# SD_Card_-_Battery_Board.net
KiCad netlist of a schematic drawn in EAGLE
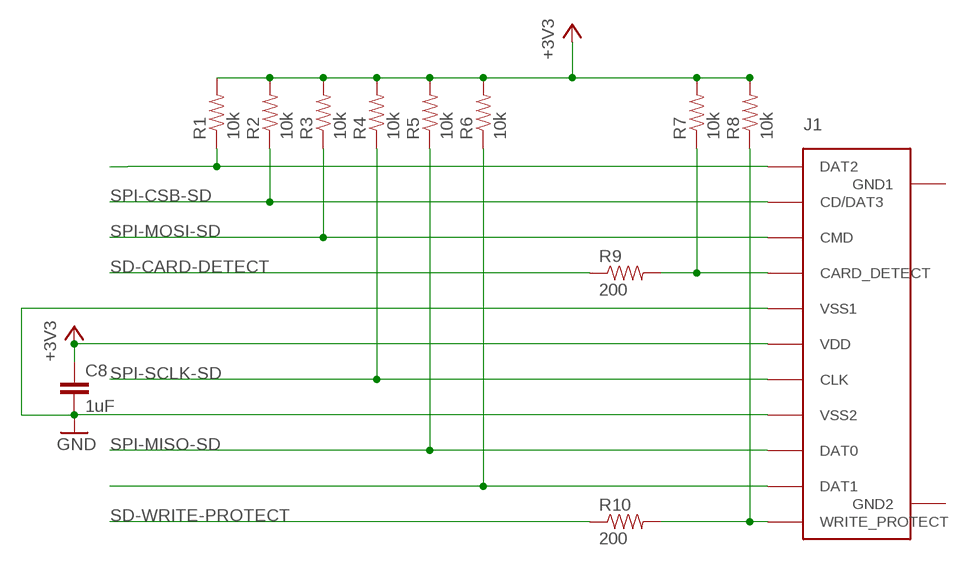
[diagram p0: schematic, sheet 1]
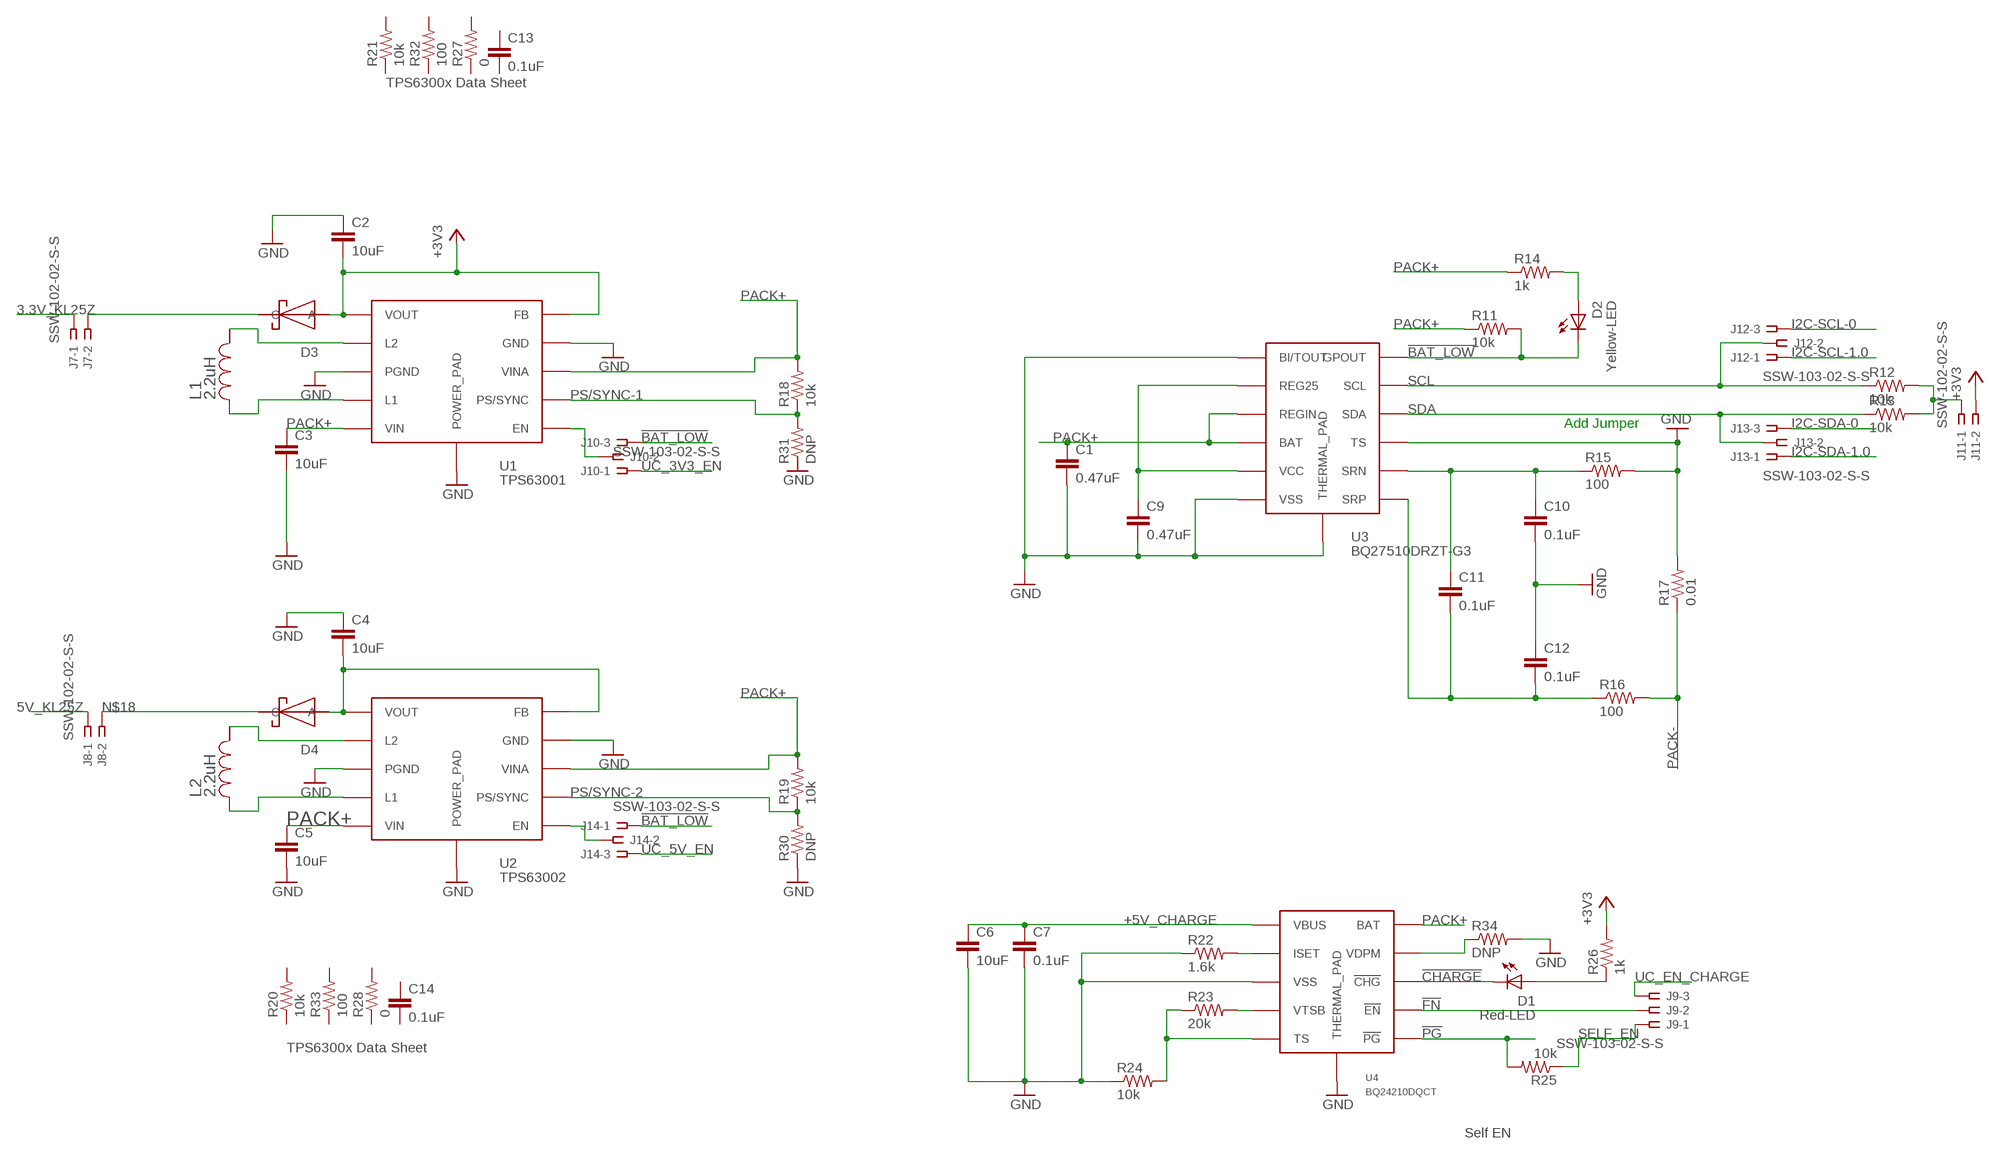
[diagram p1: schematic, sheet 2]
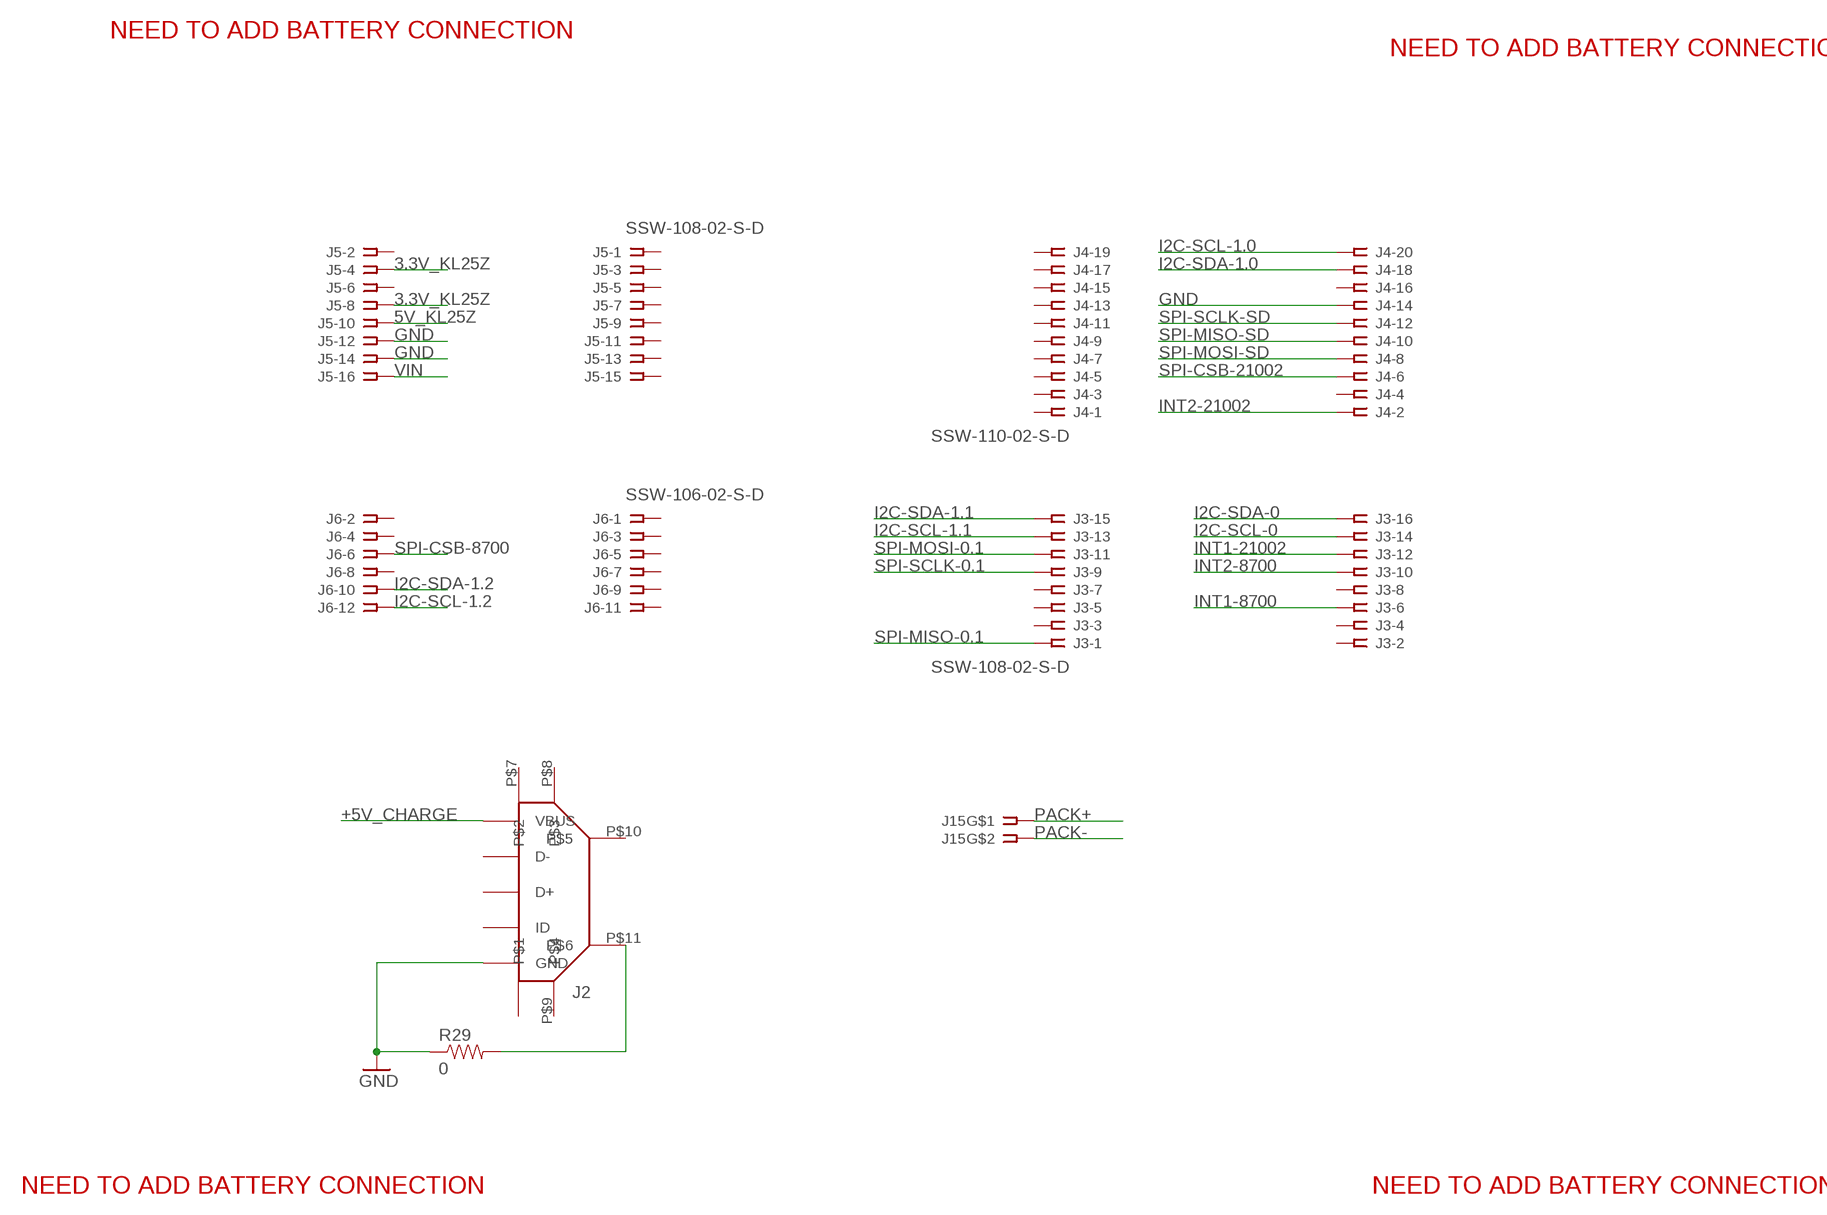
[diagram p2: schematic, sheet 3]

(export (version "E")
  (design (tool "Eeschema 10.0.6"))
  (components
    (comp (ref "C8")
      (value "1uF")
      (footprint "eagle-import:C0402")
      (fields
        (field (name "MANUFACTURER") "Johanson Dielectrics Inc.")
        (field (name "MANUFACTURER_PART_NUMBER") "100R07X105KV4T")
        (field (name "NEWARK_PART_NUMBER") "41T2953")
      )
      (libsource (lib "eagle-import") (part "CAPACITOR1U-X5R-10%-10V"))
    )
    (comp (ref "J1")
      (value "SD_CARD_SLOT")
      (footprint "eagle-import:693061010911")
      (fields
        (field (name "MANUFACTURER") "Wurth Electronik")
        (field (name "MANUFACTURER_PART_NUMBER") "693061010911")
        (field (name "NEWARK_PART_NUMBER") "89T9349")
      )
      (libsource (lib "eagle-import") (part "SD_CARD_SLOT"))
    )
    (comp (ref "R1")
      (value "10k")
      (footprint "eagle-import:R0603")
      (fields
        (field (name "MANUFACTURER") "Visay")
        (field (name "MANUFACTURER_PART_NUMBER") "TNPW060310K0DEEA")
        (field (name "NEWARK_PART_NUMBER") "84R1889")
      )
      (libsource (lib "eagle-import") (part "RESISTOR10K-100M-0.5%-75V"))
    )
    (comp (ref "R2")
      (value "10k")
      (footprint "eagle-import:R0603")
      (fields
        (field (name "MANUFACTURER") "Visay")
        (field (name "MANUFACTURER_PART_NUMBER") "TNPW060310K0DEEA")
        (field (name "NEWARK_PART_NUMBER") "84R1889")
      )
      (libsource (lib "eagle-import") (part "RESISTOR10K-100M-0.5%-75V"))
    )
    (comp (ref "R3")
      (value "10k")
      (footprint "eagle-import:R0603")
      (fields
        (field (name "MANUFACTURER") "Visay")
        (field (name "MANUFACTURER_PART_NUMBER") "TNPW060310K0DEEA")
        (field (name "NEWARK_PART_NUMBER") "84R1889")
      )
      (libsource (lib "eagle-import") (part "RESISTOR10K-100M-0.5%-75V"))
    )
    (comp (ref "R4")
      (value "10k")
      (footprint "eagle-import:R0603")
      (fields
        (field (name "MANUFACTURER") "Visay")
        (field (name "MANUFACTURER_PART_NUMBER") "TNPW060310K0DEEA")
        (field (name "NEWARK_PART_NUMBER") "84R1889")
      )
      (libsource (lib "eagle-import") (part "RESISTOR10K-100M-0.5%-75V"))
    )
    (comp (ref "R5")
      (value "10k")
      (footprint "eagle-import:R0603")
      (fields
        (field (name "MANUFACTURER") "Visay")
        (field (name "MANUFACTURER_PART_NUMBER") "TNPW060310K0DEEA")
        (field (name "NEWARK_PART_NUMBER") "84R1889")
      )
      (libsource (lib "eagle-import") (part "RESISTOR10K-100M-0.5%-75V"))
    )
    (comp (ref "R6")
      (value "10k")
      (footprint "eagle-import:R0603")
      (fields
        (field (name "MANUFACTURER") "Visay")
        (field (name "MANUFACTURER_PART_NUMBER") "TNPW060310K0DEEA")
        (field (name "NEWARK_PART_NUMBER") "84R1889")
      )
      (libsource (lib "eagle-import") (part "RESISTOR10K-100M-0.5%-75V"))
    )
    (comp (ref "R7")
      (value "10k")
      (footprint "eagle-import:R0603")
      (fields
        (field (name "MANUFACTURER") "Visay")
        (field (name "MANUFACTURER_PART_NUMBER") "TNPW060310K0DEEA")
        (field (name "NEWARK_PART_NUMBER") "84R1889")
      )
      (libsource (lib "eagle-import") (part "RESISTOR10K-100M-0.5%-75V"))
    )
    (comp (ref "R8")
      (value "10k")
      (footprint "eagle-import:R0603")
      (fields
        (field (name "MANUFACTURER") "Visay")
        (field (name "MANUFACTURER_PART_NUMBER") "TNPW060310K0DEEA")
        (field (name "NEWARK_PART_NUMBER") "84R1889")
      )
      (libsource (lib "eagle-import") (part "RESISTOR10K-100M-0.5%-75V"))
    )
    (comp (ref "R9")
      (value "200")
      (footprint "eagle-import:R0603")
      (fields
        (field (name "MANUFACTURER") "PANASONIC ELECTRONIC COMPONENTS")
        (field (name "MANUFACTURER_PART_NUMBER") "ERA-3AEB201V")
        (field (name "NEWARK_PART_NUMBER") "39P9961")
      )
      (libsource (lib "eagle-import") (part "RESISTOR200-100M-0.1%-75V"))
    )
    (comp (ref "R10")
      (value "200")
      (footprint "eagle-import:R0603")
      (fields
        (field (name "MANUFACTURER") "PANASONIC ELECTRONIC COMPONENTS")
        (field (name "MANUFACTURER_PART_NUMBER") "ERA-3AEB201V")
        (field (name "NEWARK_PART_NUMBER") "39P9961")
      )
      (libsource (lib "eagle-import") (part "RESISTOR200-100M-0.1%-75V"))
    )
    (comp (ref "J2")
      (value "USB-MICROSD-47346-001")
      (footprint "eagle-import:SD47346-001-USB-MICRO-MOLEX")
      (fields
        (field (name "MANUFACTURER") "Molex")
        (field (name "MANUFACTURER_PART_NUMBER") "SD-47346-001")
        (field (name "NEWARK_PART_NUMBER") "47M0505")
      )
      (libsource (lib "eagle-import") (part "USB-MICROSD-47346-001"))
    )
    (comp (ref "J3")
      (value "SSW-108-02-S-D")
      (footprint "eagle-import:SSW-108-02-S-D")
      (libsource (lib "eagle-import") (part "SSW-108-02-S-D"))
    )
    (comp (ref "J4")
      (value "SSW-110-02-S-D")
      (footprint "eagle-import:SSW-110-02-S-D")
      (libsource (lib "eagle-import") (part "SSW-110-02-S-D"))
    )
    (comp (ref "J5")
      (value "SSW-108-02-S-D")
      (footprint "eagle-import:SSW-108-02-S-D")
      (libsource (lib "eagle-import") (part "SSW-108-02-S-D"))
    )
    (comp (ref "J6")
      (value "SSW-106-02-S-D")
      (footprint "eagle-import:SSW-106-02-S-D")
      (libsource (lib "eagle-import") (part "SSW-106-02-S-D"))
    )
    (comp (ref "J15")
      (value "501568-0207-V2")
      (footprint "eagle-import:50156-0207")
      (fields (field (name "MANUFACTURER") "Molex"))
      (libsource (lib "eagle-import") (part "501568-0207-V2"))
    )
    (comp (ref "R29")
      (value "0")
      (footprint "eagle-import:R0402")
      (fields
        (field (name "MANUFACTURER") "PANASONIC ELECTRONIC COMPONENTS")
        (field (name "MANUFACTURER_PART_NUMBER") "ERJ-U020R00X")
        (field (name "NEWARK_PART_NUMBER") "51W3639")
      )
      (libsource (lib "eagle-import") (part "RESISTOR0-100M-X%-50V"))
    )
    (comp (ref "C1")
      (value "0.47uF")
      (footprint "eagle-import:C0402")
      (fields
        (field (name "MANUFACTURER") "Multicomp")
        (field (name "NEWARK_PART_NUMBER") "06R4896")
        (field (name "VOLTAGE") "6.3")
      )
      (libsource (lib "eagle-import") (part "CAPACITOR0.47U-X5R-10%-6.3V-0402"))
    )
    (comp (ref "C2")
      (value "10uF")
      (footprint "eagle-import:C0402")
      (fields
        (field (name "MANUFACTURER") "TDK")
        (field (name "MANUFACTURER_PART_NUMBER") "C1005X5R0J106M050BC")
        (field (name "NEWARK_PART_NUMBER") "05X9827")
      )
      (libsource (lib "eagle-import") (part "CAPACITOR10U-X5R-20%-6.3V-0402"))
    )
    (comp (ref "C3")
      (value "10uF")
      (footprint "eagle-import:C0402")
      (fields
        (field (name "MANUFACTURER") "TDK")
        (field (name "MANUFACTURER_PART_NUMBER") "C1005X5R0J106M050BC")
        (field (name "NEWARK_PART_NUMBER") "05X9827")
      )
      (libsource (lib "eagle-import") (part "CAPACITOR10U-X5R-20%-6.3V-0402"))
    )
    (comp (ref "C4")
      (value "10uF")
      (footprint "eagle-import:C0402")
      (fields
        (field (name "MANUFACTURER") "TDK")
        (field (name "MANUFACTURER_PART_NUMBER") "C1005X5R0J106M050BC")
        (field (name "NEWARK_PART_NUMBER") "05X9827")
      )
      (libsource (lib "eagle-import") (part "CAPACITOR10U-X5R-20%-6.3V-0402"))
    )
    (comp (ref "C5")
      (value "10uF")
      (footprint "eagle-import:C0402")
      (fields
        (field (name "MANUFACTURER") "TDK")
        (field (name "MANUFACTURER_PART_NUMBER") "C1005X5R0J106M050BC")
        (field (name "NEWARK_PART_NUMBER") "05X9827")
      )
      (libsource (lib "eagle-import") (part "CAPACITOR10U-X5R-20%-6.3V-0402"))
    )
    (comp (ref "C6")
      (value "10uF")
      (footprint "eagle-import:C0402")
      (fields
        (field (name "MANUFACTURER") "TDK")
        (field (name "MANUFACTURER_PART_NUMBER") "C1005X5R0J106M050BC")
        (field (name "NEWARK_PART_NUMBER") "05X9827")
      )
      (libsource (lib "eagle-import") (part "CAPACITOR10U-X5R-20%-6.3V-0402"))
    )
    (comp (ref "C7")
      (value "0.1uF")
      (footprint "eagle-import:C0402")
      (fields
        (field (name "MANUFACTURER") "TDK")
        (field (name "MANUFACTURER_PART_NUMBER") "CGA2B3X7R1E104K050BB")
        (field (name "NEWARK_PART_NUMBER") "04X3147")
      )
      (libsource (lib "eagle-import") (part "CAPACITOR0.1U-X7R-10%-25V"))
    )
    (comp (ref "C9")
      (value "0.47uF")
      (footprint "eagle-import:C0402")
      (fields
        (field (name "MANUFACTURER") "Multicomp")
        (field (name "NEWARK_PART_NUMBER") "06R4896")
        (field (name "VOLTAGE") "6.3")
      )
      (libsource (lib "eagle-import") (part "CAPACITOR0.47U-X5R-10%-6.3V-0402"))
    )
    (comp (ref "C10")
      (value "0.1uF")
      (footprint "eagle-import:C0402")
      (fields
        (field (name "MANUFACTURER") "Multicomp")
        (field (name "MANUFACTURER_PART_NUMBER") "MC0402X104K160CT")
        (field (name "NEWARK_PART_NUMBER") "06R4871")
      )
      (libsource (lib "eagle-import") (part "CAPACITOR0.1-X5R-10%-16V-0402"))
    )
    (comp (ref "C11")
      (value "0.1uF")
      (footprint "eagle-import:C0402")
      (fields
        (field (name "MANUFACTURER") "Multicomp")
        (field (name "MANUFACTURER_PART_NUMBER") "MC0402X104K160CT")
        (field (name "NEWARK_PART_NUMBER") "06R4871")
      )
      (libsource (lib "eagle-import") (part "CAPACITOR0.1-X5R-10%-16V-0402"))
    )
    (comp (ref "C12")
      (value "0.1uF")
      (footprint "eagle-import:C0402")
      (fields
        (field (name "MANUFACTURER") "Multicomp")
        (field (name "MANUFACTURER_PART_NUMBER") "MC0402X104K160CT")
        (field (name "NEWARK_PART_NUMBER") "06R4871")
      )
      (libsource (lib "eagle-import") (part "CAPACITOR0.1-X5R-10%-16V-0402"))
    )
    (comp (ref "C13")
      (value "0.1uF")
      (footprint "eagle-import:C0402")
      (fields
        (field (name "MANUFACTURER") "TDK")
        (field (name "MANUFACTURER_PART_NUMBER") "CGA2B3X7R1E104K050BB")
        (field (name "NEWARK_PART_NUMBER") "04X3147")
      )
      (libsource (lib "eagle-import") (part "CAPACITOR0.1U-X7R-10%-25V"))
    )
    (comp (ref "C14")
      (value "0.1uF")
      (footprint "eagle-import:C0402")
      (fields
        (field (name "MANUFACTURER") "TDK")
        (field (name "MANUFACTURER_PART_NUMBER") "CGA2B3X7R1E104K050BB")
        (field (name "NEWARK_PART_NUMBER") "04X3147")
      )
      (libsource (lib "eagle-import") (part "CAPACITOR0.1U-X7R-10%-25V"))
    )
    (comp (ref "D1")
      (value "Red-LED")
      (footprint "eagle-import:0.8X1.2")
      (fields
        (field (name "MANUFACTURER") "Kingbright")
        (field (name "MANUFACTURER_PART_NUMBER") "KPG-1608QBC-E")
        (field (name "NEWARK_PART_NUMBER") "56P5113")
      )
      (libsource (lib "eagle-import") (part "0.8X1.2BLUE-3.3V-20M"))
    )
    (comp (ref "D2")
      (value "Yellow-LED")
      (footprint "eagle-import:0.8X1.2")
      (fields
        (field (name "MANUFACTURER") "Kingbright")
        (field (name "MANUFACTURER_PART_NUMBER") "KPG-1608ZGC")
        (field (name "NEWARK_PART_NUMBER") "56P5117")
      )
      (libsource (lib "eagle-import") (part "0.8X1.2GREEN-3.3V-20M"))
    )
    (comp (ref "D3")
      (value "SCHOTTKY")
      (footprint "eagle-import:SC-90")
      (fields
        (field (name "MANUFACTURER") "NXP")
        (field (name "MANUFACTURER_PART_NUMBER") "PMEG2020EJ")
        (field (name "NEWARK_PART_NUMBER") "75R0865")
      )
      (libsource (lib "eagle-import") (part "SCHOTTKY"))
    )
    (comp (ref "D4")
      (value "SCHOTTKY")
      (footprint "eagle-import:SC-90")
      (fields
        (field (name "MANUFACTURER") "NXP")
        (field (name "MANUFACTURER_PART_NUMBER") "PMEG2020EJ")
        (field (name "NEWARK_PART_NUMBER") "75R0865")
      )
      (libsource (lib "eagle-import") (part "SCHOTTKY"))
    )
    (comp (ref "J7")
      (value "SSW-102-02-S-S")
      (footprint "eagle-import:SSW-102-02-S-S")
      (libsource (lib "eagle-import") (part "SSW-102-02-S-S"))
    )
    (comp (ref "J8")
      (value "SSW-102-02-S-S")
      (footprint "eagle-import:SSW-102-02-S-S")
      (libsource (lib "eagle-import") (part "SSW-102-02-S-S"))
    )
    (comp (ref "J9")
      (value "SSW-103-02-S-S")
      (footprint "eagle-import:SSW-103-02-S-S")
      (libsource (lib "eagle-import") (part "SSW-103-02-S-S"))
    )
    (comp (ref "J10")
      (value "SSW-103-02-S-S")
      (footprint "eagle-import:SSW-103-02-S-S")
      (libsource (lib "eagle-import") (part "SSW-103-02-S-S"))
    )
    (comp (ref "J11")
      (value "SSW-102-02-S-S")
      (footprint "eagle-import:SSW-102-02-S-S")
      (libsource (lib "eagle-import") (part "SSW-102-02-S-S"))
    )
    (comp (ref "J12")
      (value "SSW-103-02-S-S")
      (footprint "eagle-import:SSW-103-02-S-S")
      (libsource (lib "eagle-import") (part "SSW-103-02-S-S"))
    )
    (comp (ref "J13")
      (value "SSW-103-02-S-S")
      (footprint "eagle-import:SSW-103-02-S-S")
      (libsource (lib "eagle-import") (part "SSW-103-02-S-S"))
    )
    (comp (ref "J14")
      (value "SSW-103-02-S-S")
      (footprint "eagle-import:SSW-103-02-S-S")
      (libsource (lib "eagle-import") (part "SSW-103-02-S-S"))
    )
    (comp (ref "L1")
      (value "2.2uH")
      (footprint "eagle-import:NRS401X")
      (fields
        (field (name "MANUFACTURER") "Taiyo Yuden")
        (field (name "MANUFACTURER_PART_NUMBER") "NRS4010T2R2MDGG")
        (field (name "NEWARK_PART_NUMBER") "46T8541")
      )
      (libsource (lib "eagle-import") (part "TY0NRS4010T2R2MDGG"))
    )
    (comp (ref "L2")
      (value "2.2uH")
      (footprint "eagle-import:NRS401X")
      (fields
        (field (name "MANUFACTURER") "Taiyo Yuden")
        (field (name "MANUFACTURER_PART_NUMBER") "NRS4010T2R2MDGG")
        (field (name "NEWARK_PART_NUMBER") "46T8541")
      )
      (libsource (lib "eagle-import") (part "TY0NRS4010T2R2MDGG"))
    )
    (comp (ref "R11")
      (value "10k")
      (footprint "eagle-import:R0402")
      (fields
        (field (name "MANUFACTURER") "Yageo")
        (field (name "MANUFACTURER_PART_NUMBER") "RC0402FR-0710KL")
        (field (name "NEWARK_PART_NUMBER") "67R9884")
      )
      (libsource (lib "eagle-import") (part "RESISTOR10K-62.5M-1%-50V"))
    )
    (comp (ref "R12")
      (value "10k")
      (footprint "eagle-import:R0402")
      (fields
        (field (name "MANUFACTURER") "Yageo")
        (field (name "MANUFACTURER_PART_NUMBER") "RC0402FR-0710KL")
        (field (name "NEWARK_PART_NUMBER") "67R9884")
      )
      (libsource (lib "eagle-import") (part "RESISTOR10K-62.5M-1%-50V"))
    )
    (comp (ref "R13")
      (value "10k")
      (footprint "eagle-import:R0402")
      (fields
        (field (name "MANUFACTURER") "Yageo")
        (field (name "MANUFACTURER_PART_NUMBER") "RC0402FR-0710KL")
        (field (name "NEWARK_PART_NUMBER") "67R9884")
      )
      (libsource (lib "eagle-import") (part "RESISTOR10K-62.5M-1%-50V"))
    )
    (comp (ref "R14")
      (value "1k")
      (footprint "eagle-import:R0402")
      (fields
        (field (name "MANUFACTURER") "TE Connectivity")
        (field (name "MANUFACTURER_PART_NUMBER") "CRG0402F1K0")
        (field (name "NEWARK_PART_NUMBER") "95W7398")
      )
      (libsource (lib "eagle-import") (part "RESISTOR1K-63M-1%-50V-0402"))
    )
    (comp (ref "R15")
      (value "100")
      (footprint "eagle-import:R0402")
      (fields
        (field (name "MANUFACTURER") "TE Connectivity")
        (field (name "MANUFACTURER_PART_NUMBER") "CRG0402F1K0")
        (field (name "NEWARK_PART_NUMBER") "95W7398")
      )
      (libsource (lib "eagle-import") (part "RESISTOR1K-63M-1%-50V-0402"))
    )
    (comp (ref "R16")
      (value "100")
      (footprint "eagle-import:R0402")
      (fields
        (field (name "MANUFACTURER") "TE Connectivity")
        (field (name "MANUFACTURER_PART_NUMBER") "CRG0402F1K0")
        (field (name "NEWARK_PART_NUMBER") "95W7398")
      )
      (libsource (lib "eagle-import") (part "RESISTOR1K-63M-1%-50V-0402"))
    )
    (comp (ref "R17")
      (value "0.01")
      (footprint "eagle-import:R0603")
      (fields
        (field (name "MANUFACTURER") "Yageo")
        (field (name "MANUFACTURER_PART_NUMBER") "RL0603FR-070R01L")
        (field (name "NEWARK_PART_NUMBER") "39K1663")
      )
      (libsource (lib "eagle-import") (part "RESISTOR0.01-100M-1%-50V"))
    )
    (comp (ref "R18")
      (value "10k")
      (footprint "eagle-import:R0402")
      (fields
        (field (name "MANUFACTURER") "Yageo")
        (field (name "MANUFACTURER_PART_NUMBER") "RC0402FR-0710KL")
        (field (name "NEWARK_PART_NUMBER") "67R9884")
      )
      (libsource (lib "eagle-import") (part "RESISTOR10K-62.5M-1%-50V"))
    )
    (comp (ref "R19")
      (value "10k")
      (footprint "eagle-import:R0402")
      (fields
        (field (name "MANUFACTURER") "Yageo")
        (field (name "MANUFACTURER_PART_NUMBER") "RC0402FR-0710KL")
        (field (name "NEWARK_PART_NUMBER") "67R9884")
      )
      (libsource (lib "eagle-import") (part "RESISTOR10K-62.5M-1%-50V"))
    )
    (comp (ref "R20")
      (value "10k")
      (footprint "eagle-import:R0402")
      (fields
        (field (name "MANUFACTURER") "Yageo")
        (field (name "MANUFACTURER_PART_NUMBER") "RC0402FR-0710KL")
        (field (name "NEWARK_PART_NUMBER") "67R9884")
      )
      (libsource (lib "eagle-import") (part "RESISTOR10K-62.5M-1%-50V"))
    )
    (comp (ref "R21")
      (value "10k")
      (footprint "eagle-import:R0402")
      (fields
        (field (name "MANUFACTURER") "Yageo")
        (field (name "MANUFACTURER_PART_NUMBER") "RC0402FR-0710KL")
        (field (name "NEWARK_PART_NUMBER") "67R9884")
      )
      (libsource (lib "eagle-import") (part "RESISTOR10K-62.5M-1%-50V"))
    )
    (comp (ref "R22")
      (value "1.6k")
      (footprint "eagle-import:R0402")
      (fields
        (field (name "MANUFACTURER") "TE Connectivity")
        (field (name "MANUFACTURER_PART_NUMBER") "CRG0402F1K6")
        (field (name "NEWARK_PART_NUMBER") "95W7403")
      )
      (libsource (lib "eagle-import") (part "RESISTOR1.6K-63M-1%-50V-0402"))
    )
    (comp (ref "R23")
      (value "20k")
      (footprint "eagle-import:R0402")
      (fields
        (field (name "MANUFACTURER") "TE Connectivity")
        (field (name "MANUFACTURER_PART_NUMBER") "CRG0402F20K")
        (field (name "NEWARK_PART_NUMBER") "95W7439")
      )
      (libsource (lib "eagle-import") (part "RESISTOR20K-63M-1%-50V-0402"))
    )
    (comp (ref "R24")
      (value "10k")
      (footprint "eagle-import:R0402")
      (fields
        (field (name "MANUFACTURER") "Yageo")
        (field (name "MANUFACTURER_PART_NUMBER") "RC0402FR-0710KL")
        (field (name "NEWARK_PART_NUMBER") "67R9884")
      )
      (libsource (lib "eagle-import") (part "RESISTOR10K-62.5M-1%-50V"))
    )
    (comp (ref "R25")
      (value "10k")
      (footprint "eagle-import:R0402")
      (fields
        (field (name "MANUFACTURER") "Yageo")
        (field (name "MANUFACTURER_PART_NUMBER") "RC0402FR-0710KL")
        (field (name "NEWARK_PART_NUMBER") "67R9884")
      )
      (libsource (lib "eagle-import") (part "RESISTOR10K-62.5M-1%-50V"))
    )
    (comp (ref "R26")
      (value "1k")
      (footprint "eagle-import:R0402")
      (fields
        (field (name "MANUFACTURER") "TE Connectivity")
        (field (name "MANUFACTURER_PART_NUMBER") "CRG0402F1K0")
        (field (name "NEWARK_PART_NUMBER") "95W7398")
      )
      (libsource (lib "eagle-import") (part "RESISTOR1K-63M-1%-50V-0402"))
    )
    (comp (ref "R27")
      (value "0")
      (footprint "eagle-import:R0402")
      (fields
        (field (name "MANUFACTURER") "PANASONIC ELECTRONIC COMPONENTS")
        (field (name "MANUFACTURER_PART_NUMBER") "ERJ-U020R00X")
        (field (name "NEWARK_PART_NUMBER") "51W3639")
      )
      (libsource (lib "eagle-import") (part "RESISTOR0-100M-X%-50V"))
    )
    (comp (ref "R28")
      (value "0")
      (footprint "eagle-import:R0402")
      (fields
        (field (name "MANUFACTURER") "PANASONIC ELECTRONIC COMPONENTS")
        (field (name "MANUFACTURER_PART_NUMBER") "ERJ-U020R00X")
        (field (name "NEWARK_PART_NUMBER") "51W3639")
      )
      (libsource (lib "eagle-import") (part "RESISTOR0-100M-X%-50V"))
    )
    (comp (ref "R30")
      (value "DNP")
      (footprint "eagle-import:R0402")
      (libsource (lib "eagle-import") (part "RESISTOR0402"))
    )
    (comp (ref "R31")
      (value "DNP")
      (footprint "eagle-import:R0402")
      (libsource (lib "eagle-import") (part "RESISTOR0402"))
    )
    (comp (ref "R32")
      (value "100")
      (footprint "eagle-import:R0402")
      (fields
        (field (name "MANUFACTURER") "TE Connectivity")
        (field (name "MANUFACTURER_PART_NUMBER") "CRG0402F1K0")
        (field (name "NEWARK_PART_NUMBER") "95W7398")
      )
      (libsource (lib "eagle-import") (part "RESISTOR1K-63M-1%-50V-0402"))
    )
    (comp (ref "R33")
      (value "100")
      (footprint "eagle-import:R0402")
      (fields
        (field (name "MANUFACTURER") "TE Connectivity")
        (field (name "MANUFACTURER_PART_NUMBER") "CRG0402F1K0")
        (field (name "NEWARK_PART_NUMBER") "95W7398")
      )
      (libsource (lib "eagle-import") (part "RESISTOR1K-63M-1%-50V-0402"))
    )
    (comp (ref "R34")
      (value "DNP")
      (footprint "eagle-import:R0402")
      (libsource (lib "eagle-import") (part "RESISTOR0402"))
    )
    (comp (ref "U1")
      (value "TPS63001")
      (footprint "eagle-import:VFDFN-10")
      (fields
        (field (name "MANUFACTURER") "Texas Instuments")
        (field (name "MANUFACTURER_PART_NUMBER") "TPS63001DRCR")
        (field (name "NEWARK_PART_NUMBER") "85K1711")
      )
      (libsource (lib "eagle-import") (part "TPS6300XTPS63001"))
    )
    (comp (ref "U2")
      (value "TPS63002")
      (footprint "eagle-import:VFDFN-10")
      (fields
        (field (name "MANUFACTURER") "Texas Instuments")
        (field (name "MANUFACTURER_PART_NUMBER") "TPS63002DRCR")
        (field (name "NEWARK_PART_NUMBER") "85K1713")
      )
      (libsource (lib "eagle-import") (part "TPS6300XTPS63002"))
    )
    (comp (ref "U3")
      (value "BQ27510DRZT-G3")
      (footprint "eagle-import:VFDFN-12")
      (fields (field (name "MANUFACTURER") "Texas Instruments") (field (name "NEWARK_PART_NUMBER") "73W9727"))
      (libsource (lib "eagle-import") (part "BQ27510-G3"))
    )
    (comp (ref "U4")
      (value "BQ24210DQCT")
      (footprint "eagle-import:WFDFN-10")
      (fields (field (name "MANUFACTURER") "Texas Instruments") (field (name "NEWARK_PART_NUMBER") "56T0491"))
      (libsource (lib "eagle-import") (part "B224210"))
    )
  )
  (nets
    (net (code "1") (name "+3V3") (class "Default")
      (node (ref "C2") (pin "2") (pinfunction "2_2") (pintype "passive"))
      (node (ref "C8") (pin "1") (pinfunction "1_1") (pintype "passive"))
      (node (ref "D3") (pin "P$2") (pinfunction "A_P$2") (pintype "bidirectional"))
      (node (ref "J1") (pin "P$4") (pinfunction "VDD_P$4") (pintype "bidirectional"))
      (node (ref "J11") (pin "2") (pinfunction "1_2") (pintype "passive"))
      (node (ref "R1") (pin "2") (pinfunction "2_2") (pintype "passive"))
      (node (ref "R2") (pin "2") (pinfunction "2_2") (pintype "passive"))
      (node (ref "R26") (pin "2") (pinfunction "2_2") (pintype "passive"))
      (node (ref "R3") (pin "2") (pinfunction "2_2") (pintype "passive"))
      (node (ref "R4") (pin "2") (pinfunction "2_2") (pintype "passive"))
      (node (ref "R5") (pin "2") (pinfunction "2_2") (pintype "passive"))
      (node (ref "R6") (pin "2") (pinfunction "2_2") (pintype "passive"))
      (node (ref "R7") (pin "2") (pinfunction "2_2") (pintype "passive"))
      (node (ref "R8") (pin "2") (pinfunction "2_2") (pintype "passive"))
      (node (ref "U1") (pin "P$1") (pinfunction "VOUT_P$1") (pintype "bidirectional"))
      (node (ref "U1") (pin "P$10") (pinfunction "FB_P$10") (pintype "bidirectional"))
    )
    (net (code "2") (name "+5V_CHARGE") (class "Default")
      (node (ref "C6") (pin "1") (pinfunction "1_1") (pintype "passive"))
      (node (ref "C7") (pin "1") (pinfunction "1_1") (pintype "passive"))
      (node (ref "J2") (pin "P$1") (pinfunction "VBUS_P$1") (pintype "bidirectional"))
      (node (ref "U4") (pin "P$1") (pinfunction "VBUS_P$1") (pintype "bidirectional"))
    )
    (net (code "3") (name "3.3V_KL25Z") (class "Default")
      (node (ref "J5") (pin "4") (pinfunction "1_4") (pintype "passive"))
      (node (ref "J5") (pin "8") (pinfunction "1_8") (pintype "passive"))
      (node (ref "J7") (pin "1") (pinfunction "1_1") (pintype "passive"))
    )
    (net (code "4") (name "5V_KL25Z") (class "Default")
      (node (ref "J5") (pin "10") (pinfunction "1_10") (pintype "passive"))
      (node (ref "J8") (pin "1") (pinfunction "1_1") (pintype "passive"))
    )
    (net (code "5") (name "GND") (class "Default")
      (node (ref "C1") (pin "2") (pinfunction "2_2") (pintype "passive"))
      (node (ref "C10") (pin "2") (pinfunction "2_2") (pintype "passive"))
      (node (ref "C12") (pin "1") (pinfunction "1_1") (pintype "passive"))
      (node (ref "C2") (pin "1") (pinfunction "1_1") (pintype "passive"))
      (node (ref "C3") (pin "2") (pinfunction "2_2") (pintype "passive"))
      (node (ref "C4") (pin "1") (pinfunction "1_1") (pintype "passive"))
      (node (ref "C5") (pin "2") (pinfunction "2_2") (pintype "passive"))
      (node (ref "C6") (pin "2") (pinfunction "2_2") (pintype "passive"))
      (node (ref "C7") (pin "2") (pinfunction "2_2") (pintype "passive"))
      (node (ref "C8") (pin "2") (pinfunction "2_2") (pintype "passive"))
      (node (ref "C9") (pin "2") (pinfunction "2_2") (pintype "passive"))
      (node (ref "J1") (pin "P$3") (pinfunction "VSS1_P$3") (pintype "bidirectional"))
      (node (ref "J1") (pin "P$6") (pinfunction "VSS2_P$6") (pintype "bidirectional"))
      (node (ref "J2") (pin "P$5") (pinfunction "GND_P$5") (pintype "bidirectional"))
      (node (ref "J4") (pin "14") (pinfunction "1_14") (pintype "passive"))
      (node (ref "J5") (pin "12") (pinfunction "1_12") (pintype "passive"))
      (node (ref "J5") (pin "14") (pinfunction "1_14") (pintype "passive"))
      (node (ref "R15") (pin "2") (pinfunction "2_2") (pintype "passive"))
      (node (ref "R17") (pin "2") (pinfunction "2_2") (pintype "passive"))
      (node (ref "R22") (pin "1") (pinfunction "1_1") (pintype "passive"))
      (node (ref "R24") (pin "1") (pinfunction "1_1") (pintype "passive"))
      (node (ref "R29") (pin "1") (pinfunction "1_1") (pintype "passive"))
      (node (ref "R30") (pin "1") (pinfunction "1_1") (pintype "passive"))
      (node (ref "R31") (pin "1") (pinfunction "1_1") (pintype "passive"))
      (node (ref "R34") (pin "2") (pinfunction "2_2") (pintype "passive"))
      (node (ref "U1") (pin "P$11") (pinfunction "POWER_PAD_P$11") (pintype "bidirectional"))
      (node (ref "U1") (pin "P$3") (pinfunction "PGND_P$3") (pintype "bidirectional"))
      (node (ref "U1") (pin "P$9") (pinfunction "GND_P$9") (pintype "bidirectional"))
      (node (ref "U2") (pin "P$11") (pinfunction "POWER_PAD_P$11") (pintype "bidirectional"))
      (node (ref "U2") (pin "P$3") (pinfunction "PGND_P$3") (pintype "bidirectional"))
      (node (ref "U2") (pin "P$9") (pinfunction "GND_P$9") (pintype "bidirectional"))
      (node (ref "U3") (pin "P$1") (pinfunction "BI/TOUT_P$1") (pintype "bidirectional"))
      (node (ref "U3") (pin "P$13") (pinfunction "THERMAL_PAD_P$13") (pintype "bidirectional"))
      (node (ref "U3") (pin "P$6") (pinfunction "VSS_P$6") (pintype "bidirectional"))
      (node (ref "U3") (pin "P$9") (pinfunction "TS_P$9") (pintype "bidirectional"))
      (node (ref "U4") (pin "P$11") (pinfunction "THERMAL_PAD_P$11") (pintype "bidirectional"))
      (node (ref "U4") (pin "P$3") (pinfunction "VSS_P$3") (pintype "bidirectional"))
    )
    (net (code "6") (name "I2C-SCL-0") (class "Default")
      (node (ref "J12") (pin "3") (pinfunction "1_3") (pintype "passive"))
      (node (ref "J3") (pin "14") (pinfunction "1_14") (pintype "passive"))
    )
    (net (code "7") (name "I2C-SCL-1.0") (class "Default")
      (node (ref "J12") (pin "1") (pinfunction "1_1") (pintype "passive"))
      (node (ref "J4") (pin "20") (pinfunction "1_20") (pintype "passive"))
    )
    (net (code "8") (name "I2C-SCL-1.1") (class "Default")
      (node (ref "J3") (pin "13") (pinfunction "1_13") (pintype "passive"))
    )
    (net (code "9") (name "I2C-SCL-1.2") (class "Default")
      (node (ref "J6") (pin "12") (pinfunction "1_12") (pintype "passive"))
    )
    (net (code "10") (name "I2C-SDA-0") (class "Default")
      (node (ref "J13") (pin "3") (pinfunction "1_3") (pintype "passive"))
      (node (ref "J3") (pin "16") (pinfunction "1_16") (pintype "passive"))
    )
    (net (code "11") (name "I2C-SDA-1.0") (class "Default")
      (node (ref "J13") (pin "1") (pinfunction "1_1") (pintype "passive"))
      (node (ref "J4") (pin "18") (pinfunction "1_18") (pintype "passive"))
    )
    (net (code "12") (name "I2C-SDA-1.1") (class "Default")
      (node (ref "J3") (pin "15") (pinfunction "1_15") (pintype "passive"))
    )
    (net (code "13") (name "I2C-SDA-1.2") (class "Default")
      (node (ref "J6") (pin "10") (pinfunction "1_10") (pintype "passive"))
    )
    (net (code "14") (name "INT1-8700") (class "Default")
      (node (ref "J3") (pin "6") (pinfunction "1_6") (pintype "passive"))
    )
    (net (code "15") (name "INT1-21002") (class "Default")
      (node (ref "J3") (pin "12") (pinfunction "1_12") (pintype "passive"))
    )
    (net (code "16") (name "INT2-8700") (class "Default")
      (node (ref "J3") (pin "10") (pinfunction "1_10") (pintype "passive"))
    )
    (net (code "17") (name "INT2-21002") (class "Default")
      (node (ref "J4") (pin "2") (pinfunction "1_2") (pintype "passive"))
    )
    (net (code "18") (name "N$18") (class "Default")
      (node (ref "D4") (pin "P$1") (pinfunction "C_P$1") (pintype "bidirectional"))
      (node (ref "J8") (pin "2") (pinfunction "1_2") (pintype "passive"))
    )
    (net (code "19") (name "Net-(D1-A)") (class "Default")
      (node (ref "D1") (pin "P$1") (pinfunction "A_P$1") (pintype "bidirectional"))
      (node (ref "R26") (pin "1") (pinfunction "1_1") (pintype "passive"))
    )
    (net (code "20") (name "Net-(D2-A)") (class "Default")
      (node (ref "D2") (pin "P$1") (pinfunction "A_P$1") (pintype "bidirectional"))
      (node (ref "R14") (pin "2") (pinfunction "2_2") (pintype "passive"))
    )
    (net (code "21") (name "Net-(D3-C)") (class "Default")
      (node (ref "D3") (pin "P$1") (pinfunction "C_P$1") (pintype "bidirectional"))
      (node (ref "J7") (pin "2") (pinfunction "1_2") (pintype "passive"))
    )
    (net (code "22") (name "Net-(D4-A)") (class "Default")
      (node (ref "C4") (pin "2") (pinfunction "2_2") (pintype "passive"))
      (node (ref "D4") (pin "P$2") (pinfunction "A_P$2") (pintype "bidirectional"))
      (node (ref "U2") (pin "P$1") (pinfunction "VOUT_P$1") (pintype "bidirectional"))
      (node (ref "U2") (pin "P$10") (pinfunction "FB_P$10") (pintype "bidirectional"))
    )
    (net (code "23") (name "Net-(J1-CARD_DETECT)") (class "Default")
      (node (ref "J1") (pin "P$10") (pinfunction "CARD_DETECT_P$10") (pintype "bidirectional"))
      (node (ref "R7") (pin "1") (pinfunction "1_1") (pintype "passive"))
      (node (ref "R9") (pin "2") (pinfunction "2_2") (pintype "passive"))
    )
    (net (code "24") (name "Net-(J1-DAT1)") (class "Default")
      (node (ref "J1") (pin "P$8") (pinfunction "DAT1_P$8") (pintype "bidirectional"))
      (node (ref "R6") (pin "1") (pinfunction "1_1") (pintype "passive"))
    )
    (net (code "25") (name "Net-(J1-DAT2)") (class "Default")
      (node (ref "J1") (pin "P$9") (pinfunction "DAT2_P$9") (pintype "bidirectional"))
      (node (ref "R1") (pin "1") (pinfunction "1_1") (pintype "passive"))
    )
    (net (code "26") (name "Net-(J1-WRITE_PROTECT)") (class "Default")
      (node (ref "J1") (pin "P$11") (pinfunction "WRITE_PROTECT_P$11") (pintype "bidirectional"))
      (node (ref "R10") (pin "2") (pinfunction "2_2") (pintype "passive"))
      (node (ref "R8") (pin "1") (pinfunction "1_1") (pintype "passive"))
    )
    (net (code "27") (name "Net-(J2-P$6)") (class "Default")
      (node (ref "J2") (pin "P$11") (pinfunction "P$6_P$11") (pintype "bidirectional"))
      (node (ref "R29") (pin "2") (pinfunction "2_2") (pintype "passive"))
    )
    (net (code "28") (name "Net-(J10B-1)") (class "Default")
      (node (ref "J10") (pin "2") (pinfunction "1_2") (pintype "passive"))
      (node (ref "U1") (pin "P$6") (pinfunction "EN_P$6") (pintype "bidirectional"))
    )
    (net (code "29") (name "Net-(J11-Pad1)") (class "Default")
      (node (ref "J11") (pin "1") (pinfunction "1_1") (pintype "passive"))
      (node (ref "R12") (pin "2") (pinfunction "2_2") (pintype "passive"))
      (node (ref "R13") (pin "2") (pinfunction "2_2") (pintype "passive"))
    )
    (net (code "30") (name "Net-(J14B-1)") (class "Default")
      (node (ref "J14") (pin "2") (pinfunction "1_2") (pintype "passive"))
      (node (ref "U2") (pin "P$6") (pinfunction "EN_P$6") (pintype "bidirectional"))
    )
    (net (code "31") (name "Net-(L1-1)") (class "Default")
      (node (ref "L1") (pin "P$1") (pinfunction "1_P$1") (pintype "passive"))
      (node (ref "U1") (pin "P$2") (pinfunction "L2_P$2") (pintype "bidirectional"))
    )
    (net (code "32") (name "Net-(L1-2)") (class "Default")
      (node (ref "L1") (pin "P$2") (pinfunction "2_P$2") (pintype "passive"))
      (node (ref "U1") (pin "P$4") (pinfunction "L1_P$4") (pintype "bidirectional"))
    )
    (net (code "33") (name "Net-(L2-1)") (class "Default")
      (node (ref "L2") (pin "P$1") (pinfunction "1_P$1") (pintype "passive"))
      (node (ref "U2") (pin "P$2") (pinfunction "L2_P$2") (pintype "bidirectional"))
    )
    (net (code "34") (name "Net-(L2-2)") (class "Default")
      (node (ref "L2") (pin "P$2") (pinfunction "2_P$2") (pintype "passive"))
      (node (ref "U2") (pin "P$4") (pinfunction "L1_P$4") (pintype "bidirectional"))
    )
    (net (code "35") (name "Net-(U3-REG25)") (class "Default")
      (node (ref "C9") (pin "1") (pinfunction "1_1") (pintype "passive"))
      (node (ref "U3") (pin "P$2") (pinfunction "REG25_P$2") (pintype "bidirectional"))
      (node (ref "U3") (pin "P$5") (pinfunction "VCC_P$5") (pintype "bidirectional"))
    )
    (net (code "36") (name "Net-(U3-SRN)") (class "Default")
      (node (ref "C10") (pin "1") (pinfunction "1_1") (pintype "passive"))
      (node (ref "C11") (pin "1") (pinfunction "1_1") (pintype "passive"))
      (node (ref "R15") (pin "1") (pinfunction "1_1") (pintype "passive"))
      (node (ref "U3") (pin "P$8") (pinfunction "SRN_P$8") (pintype "bidirectional"))
    )
    (net (code "37") (name "Net-(U3-SRP)") (class "Default")
      (node (ref "C11") (pin "2") (pinfunction "2_2") (pintype "passive"))
      (node (ref "C12") (pin "2") (pinfunction "2_2") (pintype "passive"))
      (node (ref "R16") (pin "1") (pinfunction "1_1") (pintype "passive"))
      (node (ref "U3") (pin "P$7") (pinfunction "SRP_P$7") (pintype "bidirectional"))
    )
    (net (code "38") (name "Net-(U4-ISET)") (class "Default")
      (node (ref "R22") (pin "2") (pinfunction "2_2") (pintype "passive"))
      (node (ref "U4") (pin "P$2") (pinfunction "ISET_P$2") (pintype "bidirectional"))
    )
    (net (code "39") (name "Net-(U4-TS)") (class "Default")
      (node (ref "R23") (pin "1") (pinfunction "1_1") (pintype "passive"))
      (node (ref "R24") (pin "2") (pinfunction "2_2") (pintype "passive"))
      (node (ref "U4") (pin "P$5") (pinfunction "TS_P$5") (pintype "bidirectional"))
    )
    (net (code "40") (name "Net-(U4-VDPM)") (class "Default")
      (node (ref "R34") (pin "1") (pinfunction "1_1") (pintype "passive"))
      (node (ref "U4") (pin "P$9") (pinfunction "VDPM_P$9") (pintype "bidirectional"))
    )
    (net (code "41") (name "Net-(U4-VTSB)") (class "Default")
      (node (ref "R23") (pin "2") (pinfunction "2_2") (pintype "passive"))
      (node (ref "U4") (pin "P$4") (pinfunction "VTSB_P$4") (pintype "bidirectional"))
    )
    (net (code "42") (name "PACK+") (class "Default")
      (node (ref "C1") (pin "1") (pinfunction "1_1") (pintype "passive"))
      (node (ref "C3") (pin "1") (pinfunction "1_1") (pintype "passive"))
      (node (ref "C5") (pin "1") (pinfunction "1_1") (pintype "passive"))
      (node (ref "J15") (pin "P$1") (pinfunction "1_P$1") (pintype "passive"))
      (node (ref "R11") (pin "1") (pinfunction "1_1") (pintype "passive"))
      (node (ref "R14") (pin "1") (pinfunction "1_1") (pintype "passive"))
      (node (ref "R18") (pin "2") (pinfunction "2_2") (pintype "passive"))
      (node (ref "R19") (pin "2") (pinfunction "2_2") (pintype "passive"))
      (node (ref "U1") (pin "P$5") (pinfunction "VIN_P$5") (pintype "bidirectional"))
      (node (ref "U1") (pin "P$8") (pinfunction "VINA_P$8") (pintype "bidirectional"))
      (node (ref "U2") (pin "P$5") (pinfunction "VIN_P$5") (pintype "bidirectional"))
      (node (ref "U2") (pin "P$8") (pinfunction "VINA_P$8") (pintype "bidirectional"))
      (node (ref "U3") (pin "P$3") (pinfunction "REGIN_P$3") (pintype "bidirectional"))
      (node (ref "U3") (pin "P$4") (pinfunction "BAT_P$4") (pintype "bidirectional"))
      (node (ref "U4") (pin "P$10") (pinfunction "BAT_P$10") (pintype "bidirectional"))
    )
    (net (code "43") (name "PACK-") (class "Default")
      (node (ref "J15") (pin "P$2") (pinfunction "1_P$2") (pintype "passive"))
      (node (ref "R16") (pin "2") (pinfunction "2_2") (pintype "passive"))
      (node (ref "R17") (pin "1") (pinfunction "1_1") (pintype "passive"))
    )
    (net (code "44") (name "PS{slash}SYNC-1") (class "Default")
      (node (ref "R18") (pin "1") (pinfunction "1_1") (pintype "passive"))
      (node (ref "R31") (pin "2") (pinfunction "2_2") (pintype "passive"))
      (node (ref "U1") (pin "P$7") (pinfunction "PS/SYNC_P$7") (pintype "bidirectional"))
    )
    (net (code "45") (name "PS{slash}SYNC-2") (class "Default")
      (node (ref "R19") (pin "1") (pinfunction "1_1") (pintype "passive"))
      (node (ref "R30") (pin "2") (pinfunction "2_2") (pintype "passive"))
      (node (ref "U2") (pin "P$7") (pinfunction "PS/SYNC_P$7") (pintype "bidirectional"))
    )
    (net (code "46") (name "SCL") (class "Default")
      (node (ref "J12") (pin "2") (pinfunction "1_2") (pintype "passive"))
      (node (ref "R12") (pin "1") (pinfunction "1_1") (pintype "passive"))
      (node (ref "U3") (pin "P$11") (pinfunction "SCL_P$11") (pintype "bidirectional"))
    )
    (net (code "47") (name "SD-CARD-DETECT") (class "Default")
      (node (ref "R9") (pin "1") (pinfunction "1_1") (pintype "passive"))
    )
    (net (code "48") (name "SD-WRITE-PROTECT") (class "Default")
      (node (ref "R10") (pin "1") (pinfunction "1_1") (pintype "passive"))
    )
    (net (code "49") (name "SDA") (class "Default")
      (node (ref "J13") (pin "2") (pinfunction "1_2") (pintype "passive"))
      (node (ref "R13") (pin "1") (pinfunction "1_1") (pintype "passive"))
      (node (ref "U3") (pin "P$10") (pinfunction "SDA_P$10") (pintype "bidirectional"))
    )
    (net (code "50") (name "SELF_EN") (class "Default")
      (node (ref "J9") (pin "1") (pinfunction "1_1") (pintype "passive"))
      (node (ref "R25") (pin "1") (pinfunction "1_1") (pintype "passive"))
    )
    (net (code "51") (name "SPI-CSB-8700") (class "Default")
      (node (ref "J6") (pin "6") (pinfunction "1_6") (pintype "passive"))
    )
    (net (code "52") (name "SPI-CSB-21002") (class "Default")
      (node (ref "J4") (pin "6") (pinfunction "1_6") (pintype "passive"))
    )
    (net (code "53") (name "SPI-CSB-SD") (class "Default")
      (node (ref "J1") (pin "P$1") (pinfunction "CD/DAT3_P$1") (pintype "bidirectional"))
      (node (ref "R2") (pin "1") (pinfunction "1_1") (pintype "passive"))
    )
    (net (code "54") (name "SPI-MISO-0.1") (class "Default")
      (node (ref "J3") (pin "1") (pinfunction "1_1") (pintype "passive"))
    )
    (net (code "55") (name "SPI-MISO-SD") (class "Default")
      (node (ref "J1") (pin "P$7") (pinfunction "DAT0_P$7") (pintype "bidirectional"))
      (node (ref "J4") (pin "10") (pinfunction "1_10") (pintype "passive"))
      (node (ref "R5") (pin "1") (pinfunction "1_1") (pintype "passive"))
    )
    (net (code "56") (name "SPI-MOSI-0.1") (class "Default")
      (node (ref "J3") (pin "11") (pinfunction "1_11") (pintype "passive"))
    )
    (net (code "57") (name "SPI-MOSI-SD") (class "Default")
      (node (ref "J1") (pin "P$2") (pinfunction "CMD_P$2") (pintype "bidirectional"))
      (node (ref "J4") (pin "8") (pinfunction "1_8") (pintype "passive"))
      (node (ref "R3") (pin "1") (pinfunction "1_1") (pintype "passive"))
    )
    (net (code "58") (name "SPI-SCLK-0.1") (class "Default")
      (node (ref "J3") (pin "9") (pinfunction "1_9") (pintype "passive"))
    )
    (net (code "59") (name "SPI-SCLK-SD") (class "Default")
      (node (ref "J1") (pin "P$5") (pinfunction "CLK_P$5") (pintype "bidirectional"))
      (node (ref "J4") (pin "12") (pinfunction "1_12") (pintype "passive"))
      (node (ref "R4") (pin "1") (pinfunction "1_1") (pintype "passive"))
    )
    (net (code "60") (name "UC_3V3_EN") (class "Default")
      (node (ref "J10") (pin "1") (pinfunction "1_1") (pintype "passive"))
    )
    (net (code "61") (name "UC_5V_EN") (class "Default")
      (node (ref "J14") (pin "3") (pinfunction "1_3") (pintype "passive"))
    )
    (net (code "62") (name "UC_EN_CHARGE") (class "Default")
      (node (ref "J9") (pin "3") (pinfunction "1_3") (pintype "passive"))
    )
    (net (code "63") (name "VIN") (class "Default")
      (node (ref "J5") (pin "16") (pinfunction "1_16") (pintype "passive"))
    )
    (net (code "64") (name "unconnected-(C13-Pad1)") (class "Default")
      (node (ref "C13") (pin "1") (pinfunction "1_1") (pintype "passive"))
    )
    (net (code "65") (name "unconnected-(C13-Pad2)") (class "Default")
      (node (ref "C13") (pin "2") (pinfunction "2_2") (pintype "passive"))
    )
    (net (code "66") (name "unconnected-(C14-Pad1)") (class "Default")
      (node (ref "C14") (pin "1") (pinfunction "1_1") (pintype "passive"))
    )
    (net (code "67") (name "unconnected-(C14-Pad2)") (class "Default")
      (node (ref "C14") (pin "2") (pinfunction "2_2") (pintype "passive"))
    )
    (net (code "68") (name "unconnected-(J1-GND1-PadP$12)") (class "Default")
      (node (ref "J1") (pin "P$12") (pinfunction "GND1_P$12") (pintype "bidirectional"))
    )
    (net (code "69") (name "unconnected-(J1-GND2-PadP$13)") (class "Default")
      (node (ref "J1") (pin "P$13") (pinfunction "GND2_P$13") (pintype "bidirectional"))
    )
    (net (code "70") (name "unconnected-(J2-D+-PadP$3)") (class "Default")
      (node (ref "J2") (pin "P$3") (pinfunction "D+_P$3") (pintype "bidirectional"))
    )
    (net (code "71") (name "unconnected-(J2-D--PadP$2)") (class "Default")
      (node (ref "J2") (pin "P$2") (pinfunction "D-_P$2") (pintype "bidirectional"))
    )
    (net (code "72") (name "unconnected-(J2-ID-PadP$4)") (class "Default")
      (node (ref "J2") (pin "P$4") (pinfunction "ID_P$4") (pintype "bidirectional"))
    )
    (net (code "73") (name "unconnected-(J2-P$1-PadP$6)") (class "Default")
      (node (ref "J2") (pin "P$6") (pinfunction "P$1_P$6") (pintype "bidirectional"))
    )
    (net (code "74") (name "unconnected-(J2-P$2-PadP$7)") (class "Default")
      (node (ref "J2") (pin "P$7") (pinfunction "P$2_P$7") (pintype "bidirectional"))
    )
    (net (code "75") (name "unconnected-(J2-P$3-PadP$8)") (class "Default")
      (node (ref "J2") (pin "P$8") (pinfunction "P$3_P$8") (pintype "bidirectional"))
    )
    (net (code "76") (name "unconnected-(J2-P$4-PadP$9)") (class "Default")
      (node (ref "J2") (pin "P$9") (pinfunction "P$4_P$9") (pintype "bidirectional"))
    )
    (net (code "77") (name "unconnected-(J2-P$5-PadP$10)") (class "Default")
      (node (ref "J2") (pin "P$10") (pinfunction "P$5_P$10") (pintype "bidirectional"))
    )
    (net (code "78") (name "unconnected-(J3I-1-Pad2)") (class "Default")
      (node (ref "J3") (pin "2") (pinfunction "1_2") (pintype "passive"))
    )
    (net (code "79") (name "unconnected-(J3J-1-Pad3)") (class "Default")
      (node (ref "J3") (pin "3") (pinfunction "1_3") (pintype "passive"))
    )
    (net (code "80") (name "unconnected-(J3K-1-Pad4)") (class "Default")
      (node (ref "J3") (pin "4") (pinfunction "1_4") (pintype "passive"))
    )
    (net (code "81") (name "unconnected-(J3L-1-Pad5)") (class "Default")
      (node (ref "J3") (pin "5") (pinfunction "1_5") (pintype "passive"))
    )
    (net (code "82") (name "unconnected-(J3N-1-Pad7)") (class "Default")
      (node (ref "J3") (pin "7") (pinfunction "1_7") (pintype "passive"))
    )
    (net (code "83") (name "unconnected-(J3O-1-Pad8)") (class "Default")
      (node (ref "J3") (pin "8") (pinfunction "1_8") (pintype "passive"))
    )
    (net (code "84") (name "unconnected-(J4-Pad1)") (class "Default")
      (node (ref "J4") (pin "1") (pinfunction "1_1") (pintype "passive"))
    )
    (net (code "85") (name "unconnected-(J4C-1-Pad11)") (class "Default")
      (node (ref "J4") (pin "11") (pinfunction "1_11") (pintype "passive"))
    )
    (net (code "86") (name "unconnected-(J4E-1-Pad13)") (class "Default")
      (node (ref "J4") (pin "13") (pinfunction "1_13") (pintype "passive"))
    )
    (net (code "87") (name "unconnected-(J4G-1-Pad15)") (class "Default")
      (node (ref "J4") (pin "15") (pinfunction "1_15") (pintype "passive"))
    )
    (net (code "88") (name "unconnected-(J4H-1-Pad16)") (class "Default")
      (node (ref "J4") (pin "16") (pinfunction "1_16") (pintype "passive"))
    )
    (net (code "89") (name "unconnected-(J4I-1-Pad17)") (class "Default")
      (node (ref "J4") (pin "17") (pinfunction "1_17") (pintype "passive"))
    )
    (net (code "90") (name "unconnected-(J4K-1-Pad19)") (class "Default")
      (node (ref "J4") (pin "19") (pinfunction "1_19") (pintype "passive"))
    )
    (net (code "91") (name "unconnected-(J4N-1-Pad3)") (class "Default")
      (node (ref "J4") (pin "3") (pinfunction "1_3") (pintype "passive"))
    )
    (net (code "92") (name "unconnected-(J4O-1-Pad4)") (class "Default")
      (node (ref "J4") (pin "4") (pinfunction "1_4") (pintype "passive"))
    )
    (net (code "93") (name "unconnected-(J4P-1-Pad5)") (class "Default")
      (node (ref "J4") (pin "5") (pinfunction "1_5") (pintype "passive"))
    )
    (net (code "94") (name "unconnected-(J4R-1-Pad7)") (class "Default")
      (node (ref "J4") (pin "7") (pinfunction "1_7") (pintype "passive"))
    )
    (net (code "95") (name "unconnected-(J4T-1-Pad9)") (class "Default")
      (node (ref "J4") (pin "9") (pinfunction "1_9") (pintype "passive"))
    )
    (net (code "96") (name "unconnected-(J5-Pad1)") (class "Default")
      (node (ref "J5") (pin "1") (pinfunction "1_1") (pintype "passive"))
    )
    (net (code "97") (name "unconnected-(J5C-1-Pad11)") (class "Default")
      (node (ref "J5") (pin "11") (pinfunction "1_11") (pintype "passive"))
    )
    (net (code "98") (name "unconnected-(J5E-1-Pad13)") (class "Default")
      (node (ref "J5") (pin "13") (pinfunction "1_13") (pintype "passive"))
    )
    (net (code "99") (name "unconnected-(J5G-1-Pad15)") (class "Default")
      (node (ref "J5") (pin "15") (pinfunction "1_15") (pintype "passive"))
    )
    (net (code "100") (name "unconnected-(J5I-1-Pad2)") (class "Default")
      (node (ref "J5") (pin "2") (pinfunction "1_2") (pintype "passive"))
    )
    (net (code "101") (name "unconnected-(J5J-1-Pad3)") (class "Default")
      (node (ref "J5") (pin "3") (pinfunction "1_3") (pintype "passive"))
    )
    (net (code "102") (name "unconnected-(J5L-1-Pad5)") (class "Default")
      (node (ref "J5") (pin "5") (pinfunction "1_5") (pintype "passive"))
    )
    (net (code "103") (name "unconnected-(J5M-1-Pad6)") (class "Default")
      (node (ref "J5") (pin "6") (pinfunction "1_6") (pintype "passive"))
    )
    (net (code "104") (name "unconnected-(J5N-1-Pad7)") (class "Default")
      (node (ref "J5") (pin "7") (pinfunction "1_7") (pintype "passive"))
    )
    (net (code "105") (name "unconnected-(J5P-1-Pad9)") (class "Default")
      (node (ref "J5") (pin "9") (pinfunction "1_9") (pintype "passive"))
    )
    (net (code "106") (name "unconnected-(J6-Pad1)") (class "Default")
      (node (ref "J6") (pin "1") (pinfunction "1_1") (pintype "passive"))
    )
    (net (code "107") (name "unconnected-(J6C-1-Pad11)") (class "Default")
      (node (ref "J6") (pin "11") (pinfunction "1_11") (pintype "passive"))
    )
    (net (code "108") (name "unconnected-(J6E-1-Pad2)") (class "Default")
      (node (ref "J6") (pin "2") (pinfunction "1_2") (pintype "passive"))
    )
    (net (code "109") (name "unconnected-(J6F-1-Pad3)") (class "Default")
      (node (ref "J6") (pin "3") (pinfunction "1_3") (pintype "passive"))
    )
    (net (code "110") (name "unconnected-(J6G-1-Pad4)") (class "Default")
      (node (ref "J6") (pin "4") (pinfunction "1_4") (pintype "passive"))
    )
    (net (code "111") (name "unconnected-(J6H-1-Pad5)") (class "Default")
      (node (ref "J6") (pin "5") (pinfunction "1_5") (pintype "passive"))
    )
    (net (code "112") (name "unconnected-(J6J-1-Pad7)") (class "Default")
      (node (ref "J6") (pin "7") (pinfunction "1_7") (pintype "passive"))
    )
    (net (code "113") (name "unconnected-(J6K-1-Pad8)") (class "Default")
      (node (ref "J6") (pin "8") (pinfunction "1_8") (pintype "passive"))
    )
    (net (code "114") (name "unconnected-(J6L-1-Pad9)") (class "Default")
      (node (ref "J6") (pin "9") (pinfunction "1_9") (pintype "passive"))
    )
    (net (code "115") (name "unconnected-(R20-Pad1)") (class "Default")
      (node (ref "R20") (pin "1") (pinfunction "1_1") (pintype "passive"))
    )
    (net (code "116") (name "unconnected-(R20-Pad2)") (class "Default")
      (node (ref "R20") (pin "2") (pinfunction "2_2") (pintype "passive"))
    )
    (net (code "117") (name "unconnected-(R21-Pad1)") (class "Default")
      (node (ref "R21") (pin "1") (pinfunction "1_1") (pintype "passive"))
    )
    (net (code "118") (name "unconnected-(R21-Pad2)") (class "Default")
      (node (ref "R21") (pin "2") (pinfunction "2_2") (pintype "passive"))
    )
    (net (code "119") (name "unconnected-(R27-Pad1)") (class "Default")
      (node (ref "R27") (pin "1") (pinfunction "1_1") (pintype "passive"))
    )
    (net (code "120") (name "unconnected-(R27-Pad2)") (class "Default")
      (node (ref "R27") (pin "2") (pinfunction "2_2") (pintype "passive"))
    )
    (net (code "121") (name "unconnected-(R28-Pad1)") (class "Default")
      (node (ref "R28") (pin "1") (pinfunction "1_1") (pintype "passive"))
    )
    (net (code "122") (name "unconnected-(R28-Pad2)") (class "Default")
      (node (ref "R28") (pin "2") (pinfunction "2_2") (pintype "passive"))
    )
    (net (code "123") (name "unconnected-(R32-Pad1)") (class "Default")
      (node (ref "R32") (pin "1") (pinfunction "1_1") (pintype "passive"))
    )
    (net (code "124") (name "unconnected-(R32-Pad2)") (class "Default")
      (node (ref "R32") (pin "2") (pinfunction "2_2") (pintype "passive"))
    )
    (net (code "125") (name "unconnected-(R33-Pad1)") (class "Default")
      (node (ref "R33") (pin "1") (pinfunction "1_1") (pintype "passive"))
    )
    (net (code "126") (name "unconnected-(R33-Pad2)") (class "Default")
      (node (ref "R33") (pin "2") (pinfunction "2_2") (pintype "passive"))
    )
    (net (code "127") (name "~{BAT_LOW}") (class "Default")
      (node (ref "D2") (pin "P$2") (pinfunction "C_P$2") (pintype "bidirectional"))
      (node (ref "J10") (pin "3") (pinfunction "1_3") (pintype "passive"))
      (node (ref "J14") (pin "1") (pinfunction "1_1") (pintype "passive"))
      (node (ref "R11") (pin "2") (pinfunction "2_2") (pintype "passive"))
      (node (ref "U3") (pin "P$12") (pinfunction "GPOUT_P$12") (pintype "bidirectional"))
    )
    (net (code "128") (name "~{CHARGE}") (class "Default")
      (node (ref "D1") (pin "P$2") (pinfunction "C_P$2") (pintype "bidirectional"))
      (node (ref "U4") (pin "P$8") (pinfunction "~{CHG}_P$8") (pintype "bidirectional"))
    )
    (net (code "129") (name "~{FN}") (class "Default")
      (node (ref "J9") (pin "2") (pinfunction "1_2") (pintype "passive"))
      (node (ref "U4") (pin "P$7") (pinfunction "~{EN}_P$7") (pintype "bidirectional"))
    )
    (net (code "130") (name "~{PG}") (class "Default")
      (node (ref "R25") (pin "2") (pinfunction "2_2") (pintype "passive"))
      (node (ref "U4") (pin "P$6") (pinfunction "~{PG}_P$6") (pintype "bidirectional"))
    )
  )
)
